# DC075B_LVDS_OUTPUT.net
KiCad netlist of a schematic drawn in Altium Designer
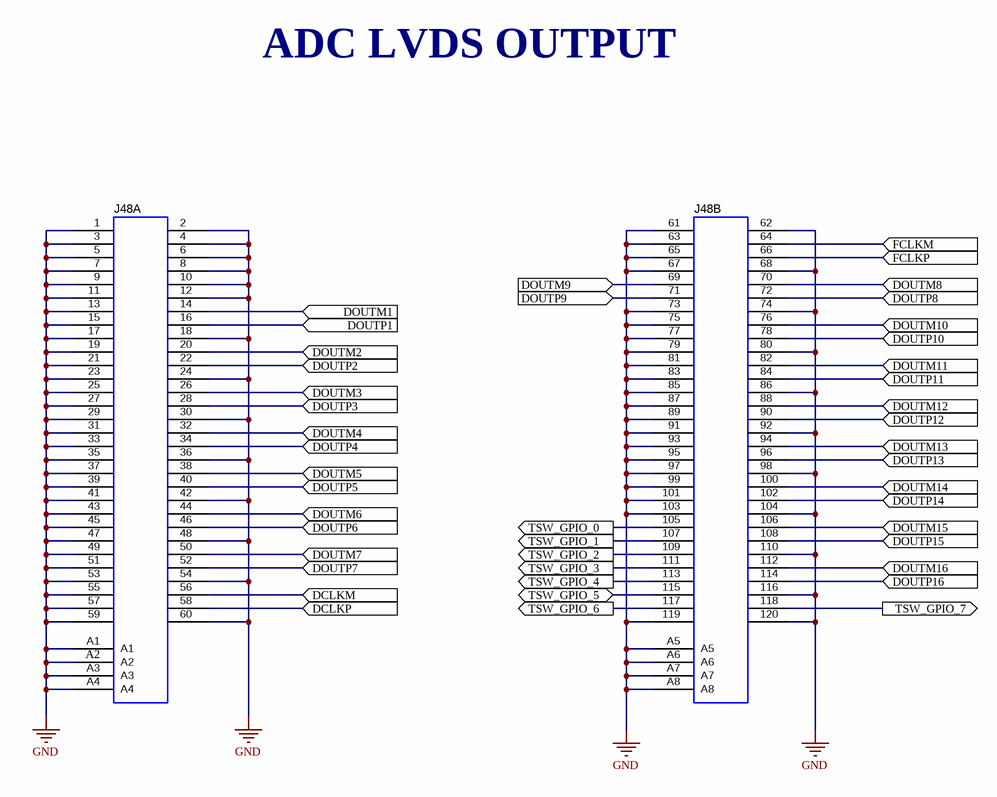
[diagram p0: DC075B_LVDS_OUTPUT.SchDoc]

(export (version "E")
  (design (tool "Eeschema 10.0.6"))
  (components
    (comp (ref "J48")
      (value "SAMTEC_QTH-060-01-L-D-A")
      (footprint "SAMTEC_QTH-060-01-L-D-A")
      (description "Socket, 0.5MM, 60x2, Gold, SMT")
      (fields (field (name "PARTNUMBER") "QTH-060-01-L-D-A") (field (name "MANUFACTURER") "Samtec"))
      (libsource (lib "Altium Vault - TI") (part "SAMTEC_QTH-060-01-L-D-A"))
    )
  )
  (nets
    (net (code "1") (name "/DCLKM") (class "Default")
      (node (ref "J48") (pin "56") (pinfunction "56_56") (pintype "passive"))
    )
    (net (code "2") (name "/DCLKP") (class "Default")
      (node (ref "J48") (pin "58") (pinfunction "58_58") (pintype "passive"))
    )
    (net (code "3") (name "/DOUTM1") (class "Default")
      (node (ref "J48") (pin "14") (pinfunction "14_14") (pintype "passive"))
    )
    (net (code "4") (name "/DOUTM2") (class "Default")
      (node (ref "J48") (pin "20") (pinfunction "20_20") (pintype "passive"))
    )
    (net (code "5") (name "/DOUTM3") (class "Default")
      (node (ref "J48") (pin "26") (pinfunction "26_26") (pintype "passive"))
    )
    (net (code "6") (name "/DOUTM4") (class "Default")
      (node (ref "J48") (pin "32") (pinfunction "32_32") (pintype "passive"))
    )
    (net (code "7") (name "/DOUTM5") (class "Default")
      (node (ref "J48") (pin "38") (pinfunction "38_38") (pintype "passive"))
    )
    (net (code "8") (name "/DOUTM6") (class "Default")
      (node (ref "J48") (pin "44") (pinfunction "44_44") (pintype "passive"))
    )
    (net (code "9") (name "/DOUTM7") (class "Default")
      (node (ref "J48") (pin "50") (pinfunction "50_50") (pintype "passive"))
    )
    (net (code "10") (name "/DOUTM8") (class "Default")
      (node (ref "J48") (pin "70") (pinfunction "70_70") (pintype "passive"))
    )
    (net (code "11") (name "/DOUTM9") (class "Default")
      (node (ref "J48") (pin "69") (pinfunction "69_69") (pintype "passive"))
    )
    (net (code "12") (name "/DOUTM10") (class "Default")
      (node (ref "J48") (pin "76") (pinfunction "76_76") (pintype "passive"))
    )
    (net (code "13") (name "/DOUTM11") (class "Default")
      (node (ref "J48") (pin "82") (pinfunction "82_82") (pintype "passive"))
    )
    (net (code "14") (name "/DOUTM12") (class "Default")
      (node (ref "J48") (pin "88") (pinfunction "88_88") (pintype "passive"))
    )
    (net (code "15") (name "/DOUTM13") (class "Default")
      (node (ref "J48") (pin "94") (pinfunction "94_94") (pintype "passive"))
    )
    (net (code "16") (name "/DOUTM14") (class "Default")
      (node (ref "J48") (pin "100") (pinfunction "100_100") (pintype "passive"))
    )
    (net (code "17") (name "/DOUTM15") (class "Default")
      (node (ref "J48") (pin "106") (pinfunction "106_106") (pintype "passive"))
    )
    (net (code "18") (name "/DOUTM16") (class "Default")
      (node (ref "J48") (pin "112") (pinfunction "112_112") (pintype "passive"))
    )
    (net (code "19") (name "/DOUTP1") (class "Default")
      (node (ref "J48") (pin "16") (pinfunction "16_16") (pintype "passive"))
    )
    (net (code "20") (name "/DOUTP2") (class "Default")
      (node (ref "J48") (pin "22") (pinfunction "22_22") (pintype "passive"))
    )
    (net (code "21") (name "/DOUTP3") (class "Default")
      (node (ref "J48") (pin "28") (pinfunction "28_28") (pintype "passive"))
    )
    (net (code "22") (name "/DOUTP4") (class "Default")
      (node (ref "J48") (pin "34") (pinfunction "34_34") (pintype "passive"))
    )
    (net (code "23") (name "/DOUTP5") (class "Default")
      (node (ref "J48") (pin "40") (pinfunction "40_40") (pintype "passive"))
    )
    (net (code "24") (name "/DOUTP6") (class "Default")
      (node (ref "J48") (pin "46") (pinfunction "46_46") (pintype "passive"))
    )
    (net (code "25") (name "/DOUTP7") (class "Default")
      (node (ref "J48") (pin "52") (pinfunction "52_52") (pintype "passive"))
    )
    (net (code "26") (name "/DOUTP8") (class "Default")
      (node (ref "J48") (pin "72") (pinfunction "72_72") (pintype "passive"))
    )
    (net (code "27") (name "/DOUTP9") (class "Default")
      (node (ref "J48") (pin "71") (pinfunction "71_71") (pintype "passive"))
    )
    (net (code "28") (name "/DOUTP10") (class "Default")
      (node (ref "J48") (pin "78") (pinfunction "78_78") (pintype "passive"))
    )
    (net (code "29") (name "/DOUTP11") (class "Default")
      (node (ref "J48") (pin "84") (pinfunction "84_84") (pintype "passive"))
    )
    (net (code "30") (name "/DOUTP12") (class "Default")
      (node (ref "J48") (pin "90") (pinfunction "90_90") (pintype "passive"))
    )
    (net (code "31") (name "/DOUTP13") (class "Default")
      (node (ref "J48") (pin "96") (pinfunction "96_96") (pintype "passive"))
    )
    (net (code "32") (name "/DOUTP14") (class "Default")
      (node (ref "J48") (pin "102") (pinfunction "102_102") (pintype "passive"))
    )
    (net (code "33") (name "/DOUTP15") (class "Default")
      (node (ref "J48") (pin "108") (pinfunction "108_108") (pintype "passive"))
    )
    (net (code "34") (name "/DOUTP16") (class "Default")
      (node (ref "J48") (pin "114") (pinfunction "114_114") (pintype "passive"))
    )
    (net (code "35") (name "/FCLKM") (class "Default")
      (node (ref "J48") (pin "64") (pinfunction "64_64") (pintype "passive"))
    )
    (net (code "36") (name "/FCLKP") (class "Default")
      (node (ref "J48") (pin "66") (pinfunction "66_66") (pintype "passive"))
    )
    (net (code "37") (name "/TSW_GPIO_0") (class "Default")
      (node (ref "J48") (pin "105") (pinfunction "105_105") (pintype "passive"))
    )
    (net (code "38") (name "/TSW_GPIO_1") (class "Default")
      (node (ref "J48") (pin "107") (pinfunction "107_107") (pintype "passive"))
    )
    (net (code "39") (name "/TSW_GPIO_2") (class "Default")
      (node (ref "J48") (pin "109") (pinfunction "109_109") (pintype "passive"))
    )
    (net (code "40") (name "/TSW_GPIO_3") (class "Default")
      (node (ref "J48") (pin "111") (pinfunction "111_111") (pintype "passive"))
    )
    (net (code "41") (name "/TSW_GPIO_4") (class "Default")
      (node (ref "J48") (pin "113") (pinfunction "113_113") (pintype "passive"))
    )
    (net (code "42") (name "/TSW_GPIO_5") (class "Default")
      (node (ref "J48") (pin "115") (pinfunction "115_115") (pintype "passive"))
    )
    (net (code "43") (name "/TSW_GPIO_6") (class "Default")
      (node (ref "J48") (pin "117") (pinfunction "117_117") (pintype "passive"))
    )
    (net (code "44") (name "/TSW_GPIO_7") (class "Default")
      (node (ref "J48") (pin "118") (pinfunction "118_118") (pintype "passive"))
    )
    (net (code "45") (name "GND") (class "Default")
      (node (ref "J48") (pin "1") (pinfunction "1_1") (pintype "passive"))
      (node (ref "J48") (pin "10") (pinfunction "10_10") (pintype "passive"))
      (node (ref "J48") (pin "101") (pinfunction "101_101") (pintype "passive"))
      (node (ref "J48") (pin "103") (pinfunction "103_103") (pintype "passive"))
      (node (ref "J48") (pin "104") (pinfunction "104_104") (pintype "passive"))
      (node (ref "J48") (pin "11") (pinfunction "11_11") (pintype "passive"))
      (node (ref "J48") (pin "110") (pinfunction "110_110") (pintype "passive"))
      (node (ref "J48") (pin "116") (pinfunction "116_116") (pintype "passive"))
      (node (ref "J48") (pin "119") (pinfunction "119_119") (pintype "passive"))
      (node (ref "J48") (pin "12") (pinfunction "12_12") (pintype "passive"))
      (node (ref "J48") (pin "120") (pinfunction "120_120") (pintype "passive"))
      (node (ref "J48") (pin "13") (pinfunction "13_13") (pintype "passive"))
      (node (ref "J48") (pin "15") (pinfunction "15_15") (pintype "passive"))
      (node (ref "J48") (pin "17") (pinfunction "17_17") (pintype "passive"))
      (node (ref "J48") (pin "18") (pinfunction "18_18") (pintype "passive"))
      (node (ref "J48") (pin "19") (pinfunction "19_19") (pintype "passive"))
      (node (ref "J48") (pin "2") (pinfunction "2_2") (pintype "passive"))
      (node (ref "J48") (pin "21") (pinfunction "21_21") (pintype "passive"))
      (node (ref "J48") (pin "23") (pinfunction "23_23") (pintype "passive"))
      (node (ref "J48") (pin "24") (pinfunction "24_24") (pintype "passive"))
      (node (ref "J48") (pin "25") (pinfunction "25_25") (pintype "passive"))
      (node (ref "J48") (pin "27") (pinfunction "27_27") (pintype "passive"))
      (node (ref "J48") (pin "29") (pinfunction "29_29") (pintype "passive"))
      (node (ref "J48") (pin "3") (pinfunction "3_3") (pintype "passive"))
      (node (ref "J48") (pin "30") (pinfunction "30_30") (pintype "passive"))
      (node (ref "J48") (pin "31") (pinfunction "31_31") (pintype "passive"))
      (node (ref "J48") (pin "33") (pinfunction "33_33") (pintype "passive"))
      (node (ref "J48") (pin "35") (pinfunction "35_35") (pintype "passive"))
      (node (ref "J48") (pin "36") (pinfunction "36_36") (pintype "passive"))
      (node (ref "J48") (pin "37") (pinfunction "37_37") (pintype "passive"))
      (node (ref "J48") (pin "39") (pinfunction "39_39") (pintype "passive"))
      (node (ref "J48") (pin "4") (pinfunction "4_4") (pintype "passive"))
      (node (ref "J48") (pin "41") (pinfunction "41_41") (pintype "passive"))
      (node (ref "J48") (pin "42") (pinfunction "42_42") (pintype "passive"))
      (node (ref "J48") (pin "43") (pinfunction "43_43") (pintype "passive"))
      (node (ref "J48") (pin "45") (pinfunction "45_45") (pintype "passive"))
      (node (ref "J48") (pin "47") (pinfunction "47_47") (pintype "passive"))
      (node (ref "J48") (pin "48") (pinfunction "48_48") (pintype "passive"))
      (node (ref "J48") (pin "49") (pinfunction "49_49") (pintype "passive"))
      (node (ref "J48") (pin "5") (pinfunction "5_5") (pintype "passive"))
      (node (ref "J48") (pin "51") (pinfunction "51_51") (pintype "passive"))
      (node (ref "J48") (pin "53") (pinfunction "53_53") (pintype "passive"))
      (node (ref "J48") (pin "54") (pinfunction "54_54") (pintype "passive"))
      (node (ref "J48") (pin "55") (pinfunction "55_55") (pintype "passive"))
      (node (ref "J48") (pin "57") (pinfunction "57_57") (pintype "passive"))
      (node (ref "J48") (pin "59") (pinfunction "59_59") (pintype "passive"))
      (node (ref "J48") (pin "6") (pinfunction "6_6") (pintype "passive"))
      (node (ref "J48") (pin "60") (pinfunction "60_60") (pintype "passive"))
      (node (ref "J48") (pin "61") (pinfunction "61_61") (pintype "passive"))
      (node (ref "J48") (pin "62") (pinfunction "62_62") (pintype "passive"))
      (node (ref "J48") (pin "63") (pinfunction "63_63") (pintype "passive"))
      (node (ref "J48") (pin "65") (pinfunction "65_65") (pintype "passive"))
      (node (ref "J48") (pin "67") (pinfunction "67_67") (pintype "passive"))
      (node (ref "J48") (pin "68") (pinfunction "68_68") (pintype "passive"))
      (node (ref "J48") (pin "7") (pinfunction "7_7") (pintype "passive"))
      (node (ref "J48") (pin "73") (pinfunction "73_73") (pintype "passive"))
      (node (ref "J48") (pin "74") (pinfunction "74_74") (pintype "passive"))
      (node (ref "J48") (pin "75") (pinfunction "75_75") (pintype "passive"))
      (node (ref "J48") (pin "77") (pinfunction "77_77") (pintype "passive"))
      (node (ref "J48") (pin "79") (pinfunction "79_79") (pintype "passive"))
      (node (ref "J48") (pin "8") (pinfunction "8_8") (pintype "passive"))
      (node (ref "J48") (pin "80") (pinfunction "80_80") (pintype "passive"))
      (node (ref "J48") (pin "81") (pinfunction "81_81") (pintype "passive"))
      (node (ref "J48") (pin "83") (pinfunction "83_83") (pintype "passive"))
      (node (ref "J48") (pin "85") (pinfunction "85_85") (pintype "passive"))
      (node (ref "J48") (pin "86") (pinfunction "86_86") (pintype "passive"))
      (node (ref "J48") (pin "87") (pinfunction "87_87") (pintype "passive"))
      (node (ref "J48") (pin "89") (pinfunction "89_89") (pintype "passive"))
      (node (ref "J48") (pin "9") (pinfunction "9_9") (pintype "passive"))
      (node (ref "J48") (pin "91") (pinfunction "91_91") (pintype "passive"))
      (node (ref "J48") (pin "92") (pinfunction "92_92") (pintype "passive"))
      (node (ref "J48") (pin "93") (pinfunction "93_93") (pintype "passive"))
      (node (ref "J48") (pin "95") (pinfunction "95_95") (pintype "passive"))
      (node (ref "J48") (pin "97") (pinfunction "97_97") (pintype "passive"))
      (node (ref "J48") (pin "98") (pinfunction "98_98") (pintype "passive"))
      (node (ref "J48") (pin "99") (pinfunction "99_99") (pintype "passive"))
      (node (ref "J48") (pin "A1") (pinfunction "A1_A1") (pintype "power_in"))
      (node (ref "J48") (pin "A2") (pinfunction "A2_A2") (pintype "power_in"))
      (node (ref "J48") (pin "A3") (pinfunction "A3_A3") (pintype "power_in"))
      (node (ref "J48") (pin "A4") (pinfunction "A4_A4") (pintype "power_in"))
      (node (ref "J48") (pin "A5") (pinfunction "A5_A5") (pintype "power_in"))
      (node (ref "J48") (pin "A6") (pinfunction "A6_A6") (pintype "power_in"))
      (node (ref "J48") (pin "A7") (pinfunction "A7_A7") (pintype "power_in"))
      (node (ref "J48") (pin "A8") (pinfunction "A8_A8") (pintype "power_in"))
    )
  )
)
